# EEPROM.net
KiCad netlist of a schematic drawn in Altium Designer
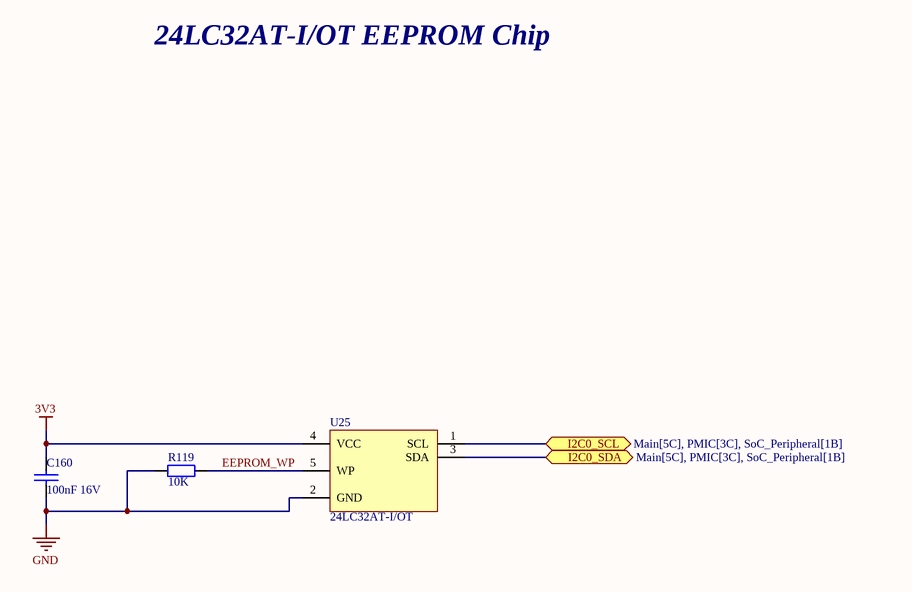
[diagram p0: EEPROM.SchDoc]

(export (version "E")
  (design (tool "Eeschema 10.0.6"))
  (components
    (comp (ref "C160")
      (value "100nF 16V")
      (footprint "C_0402")
      (description "Capacitor 0402 SMD")
      (libsource (lib "tor1kkLib") (part "C_0402"))
    )
    (comp (ref "R119")
      (value "10K")
      (footprint "R_0402")
      (description "Resistor 0402 SMD")
      (libsource (lib "tor1kkLib") (part "R_0402"))
    )
    (comp (ref "U25")
      (value "24LC32AT-I/OT")
      (footprint "SOT-23-5")
      (description "32Kbit 400kHz I2C SOT-23-5 EEPROM ROHS")
      (fields (field (name "MANUFACTURER") "Microchip Tech"))
      (libsource (lib "tor1kkLib") (part "24LC32AT-I/OT"))
    )
  )
  (nets
    (net (code "1") (name "/EEPROM_WP") (class "Default")
      (node (ref "R119") (pin "1") (pintype "passive"))
      (node (ref "U25") (pin "5") (pinfunction "WP_5") (pintype "passive"))
    )
    (net (code "2") (name "/I2C0_SCL") (class "Default")
      (node (ref "U25") (pin "1") (pinfunction "SCL_1") (pintype "passive"))
    )
    (net (code "3") (name "/I2C0_SDA") (class "Default")
      (node (ref "U25") (pin "3") (pinfunction "SDA_3") (pintype "passive"))
    )
    (net (code "4") (name "3V3") (class "Default")
      (node (ref "C160") (pin "1") (pintype "passive"))
      (node (ref "U25") (pin "4") (pinfunction "VCC_4") (pintype "passive"))
    )
    (net (code "5") (name "GND") (class "Default")
      (node (ref "C160") (pin "2") (pintype "passive"))
      (node (ref "R119") (pin "2") (pintype "passive"))
      (node (ref "U25") (pin "2") (pinfunction "GND_2") (pintype "passive"))
    )
  )
)
